# secondary_DIO.net
KiCad netlist of a schematic drawn in Altium Designer
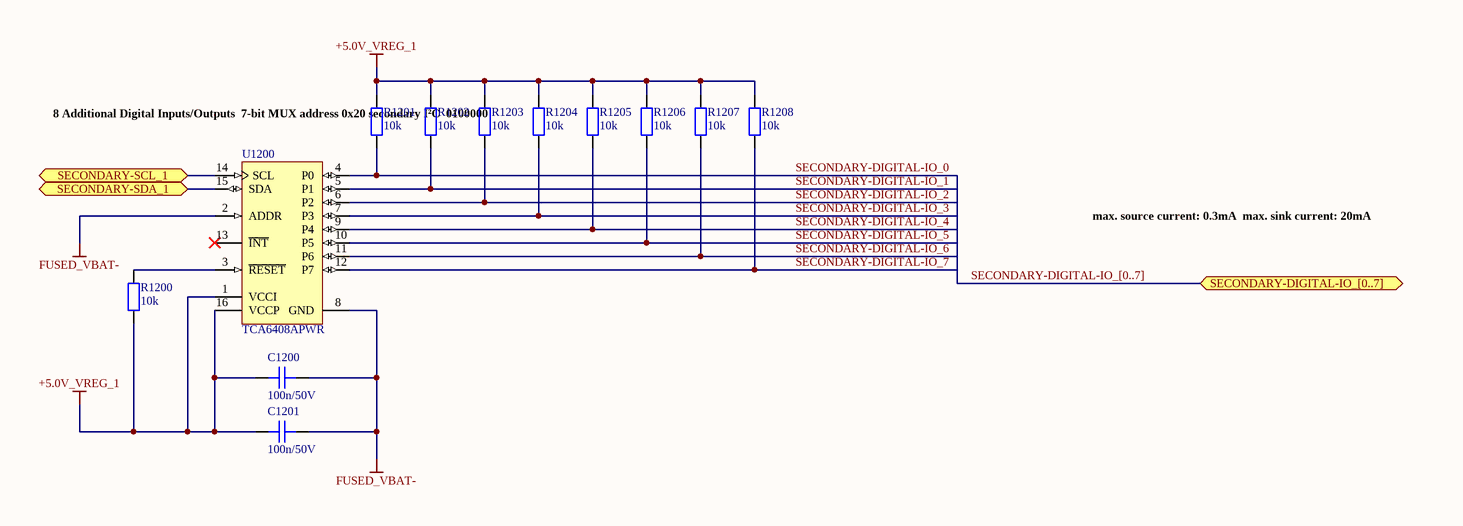
[diagram p0: secondary_DIO.SchDoc]

(export (version "E")
  (design (tool "Eeschema 10.0.6"))
  (components
    (comp (ref "C1200")
      (value "100n/50V")
      (footprint "CAPC1608X08N")
      (description "MLCC")
      (fields (field (name "PART NUMBER") "gen_C_ceramic_100n_50V_X7R_0603"))
      (libsource (lib "OE750") (part "C"))
    )
    (comp (ref "C1201")
      (value "100n/50V")
      (footprint "CAPC1608X08N")
      (description "MLCC")
      (fields (field (name "PART NUMBER") "gen_C_ceramic_100n_50V_X7R_0603"))
      (libsource (lib "OE750") (part "C"))
    )
    (comp (ref "R1200")
      (value "10k")
      (footprint "RESC1608X05N")
      (description "SMD Resistor 10k 0603")
      (fields (field (name "PART NUMBER") "gen_R_10k_0603") (field (name "TOLERANCE") "1%"))
      (libsource (lib "OE750") (part "R"))
    )
    (comp (ref "R1201")
      (value "10k")
      (footprint "RESC1608X05N")
      (description "SMD Resistor 10k 0603")
      (fields (field (name "PART NUMBER") "gen_R_10k_0603") (field (name "TOLERANCE") "1%"))
      (libsource (lib "OE750") (part "R"))
    )
    (comp (ref "R1202")
      (value "10k")
      (footprint "RESC1608X05N")
      (description "SMD Resistor 10k 0603")
      (fields (field (name "PART NUMBER") "gen_R_10k_0603") (field (name "TOLERANCE") "1%"))
      (libsource (lib "OE750") (part "R"))
    )
    (comp (ref "R1203")
      (value "10k")
      (footprint "RESC1608X05N")
      (description "SMD Resistor 10k 0603")
      (fields (field (name "PART NUMBER") "gen_R_10k_0603") (field (name "TOLERANCE") "1%"))
      (libsource (lib "OE750") (part "R"))
    )
    (comp (ref "R1204")
      (value "10k")
      (footprint "RESC1608X05N")
      (description "SMD Resistor 10k 0603")
      (fields (field (name "PART NUMBER") "gen_R_10k_0603") (field (name "TOLERANCE") "1%"))
      (libsource (lib "OE750") (part "R"))
    )
    (comp (ref "R1205")
      (value "10k")
      (footprint "RESC1608X05N")
      (description "SMD Resistor 10k 0603")
      (fields (field (name "PART NUMBER") "gen_R_10k_0603") (field (name "TOLERANCE") "1%"))
      (libsource (lib "OE750") (part "R"))
    )
    (comp (ref "R1206")
      (value "10k")
      (footprint "RESC1608X05N")
      (description "SMD Resistor 10k 0603")
      (fields (field (name "PART NUMBER") "gen_R_10k_0603") (field (name "TOLERANCE") "1%"))
      (libsource (lib "OE750") (part "R"))
    )
    (comp (ref "R1207")
      (value "10k")
      (footprint "RESC1608X05N")
      (description "SMD Resistor 10k 0603")
      (fields (field (name "PART NUMBER") "gen_R_10k_0603") (field (name "TOLERANCE") "1%"))
      (libsource (lib "OE750") (part "R"))
    )
    (comp (ref "R1208")
      (value "10k")
      (footprint "RESC1608X05N")
      (description "SMD Resistor 10k 0603")
      (fields (field (name "PART NUMBER") "gen_R_10k_0603") (field (name "TOLERANCE") "1%"))
      (libsource (lib "OE750") (part "R"))
    )
    (comp (ref "U1200")
      (value "TCA6408APWR")
      (footprint "PW0016A_L")
      (fields (field (name "MANUFACTURER") "Texas Instruments"))
      (libsource (lib "Altium Content Vault") (part "TI-TCA6408A-TSSOP_PW-16"))
    )
  )
  (nets
    (net (code "1") (name "+5.0V_VREG_1") (class "Default")
      (node (ref "C1200") (pin "2") (pinfunction "2_2") (pintype "passive"))
      (node (ref "C1201") (pin "2") (pinfunction "2_2") (pintype "passive"))
      (node (ref "R1200") (pin "1") (pinfunction "1_1") (pintype "passive"))
      (node (ref "R1201") (pin "2") (pinfunction "2_2") (pintype "passive"))
      (node (ref "R1202") (pin "2") (pinfunction "2_2") (pintype "passive"))
      (node (ref "R1203") (pin "2") (pinfunction "2_2") (pintype "passive"))
      (node (ref "R1204") (pin "2") (pinfunction "2_2") (pintype "passive"))
      (node (ref "R1205") (pin "2") (pinfunction "2_2") (pintype "passive"))
      (node (ref "R1206") (pin "2") (pinfunction "2_2") (pintype "passive"))
      (node (ref "R1207") (pin "2") (pinfunction "2_2") (pintype "passive"))
      (node (ref "R1208") (pin "2") (pinfunction "2_2") (pintype "passive"))
      (node (ref "U1200") (pin "1") (pinfunction "VCCI_1") (pintype "power_in"))
      (node (ref "U1200") (pin "16") (pinfunction "VCCP_16") (pintype "power_in"))
    )
    (net (code "2") (name "/SECONDARY-DIGITAL-IO_0") (class "Default")
      (node (ref "R1201") (pin "1") (pinfunction "1_1") (pintype "passive"))
      (node (ref "U1200") (pin "4") (pinfunction "P0_4") (pintype "bidirectional"))
    )
    (net (code "3") (name "/SECONDARY-DIGITAL-IO_1") (class "Default")
      (node (ref "R1202") (pin "1") (pinfunction "1_1") (pintype "passive"))
      (node (ref "U1200") (pin "5") (pinfunction "P1_5") (pintype "bidirectional"))
    )
    (net (code "4") (name "/SECONDARY-DIGITAL-IO_2") (class "Default")
      (node (ref "R1203") (pin "1") (pinfunction "1_1") (pintype "passive"))
      (node (ref "U1200") (pin "6") (pinfunction "P2_6") (pintype "bidirectional"))
    )
    (net (code "5") (name "/SECONDARY-DIGITAL-IO_3") (class "Default")
      (node (ref "R1204") (pin "1") (pinfunction "1_1") (pintype "passive"))
      (node (ref "U1200") (pin "7") (pinfunction "P3_7") (pintype "bidirectional"))
    )
    (net (code "6") (name "/SECONDARY-DIGITAL-IO_4") (class "Default")
      (node (ref "R1205") (pin "1") (pinfunction "1_1") (pintype "passive"))
      (node (ref "U1200") (pin "9") (pinfunction "P4_9") (pintype "bidirectional"))
    )
    (net (code "7") (name "/SECONDARY-DIGITAL-IO_5") (class "Default")
      (node (ref "R1206") (pin "1") (pinfunction "1_1") (pintype "passive"))
      (node (ref "U1200") (pin "10") (pinfunction "P5_10") (pintype "bidirectional"))
    )
    (net (code "8") (name "/SECONDARY-DIGITAL-IO_6") (class "Default")
      (node (ref "R1207") (pin "1") (pinfunction "1_1") (pintype "passive"))
      (node (ref "U1200") (pin "11") (pinfunction "P6_11") (pintype "bidirectional"))
    )
    (net (code "9") (name "/SECONDARY-DIGITAL-IO_7") (class "Default")
      (node (ref "R1208") (pin "1") (pinfunction "1_1") (pintype "passive"))
      (node (ref "U1200") (pin "12") (pinfunction "P7_12") (pintype "bidirectional"))
    )
    (net (code "11") (name "/SECONDARY-SCL_1") (class "Default")
      (node (ref "U1200") (pin "14") (pinfunction "SCL_14") (pintype "input"))
    )
    (net (code "12") (name "/SECONDARY-SDA_1") (class "Default")
      (node (ref "U1200") (pin "15") (pinfunction "SDA_15") (pintype "bidirectional"))
    )
    (net (code "13") (name "FUSED_VBAT-") (class "Default")
      (node (ref "C1200") (pin "1") (pinfunction "1_1") (pintype "passive"))
      (node (ref "C1201") (pin "1") (pinfunction "1_1") (pintype "passive"))
      (node (ref "U1200") (pin "2") (pinfunction "ADDR_2") (pintype "input"))
      (node (ref "U1200") (pin "8") (pinfunction "GND_8") (pintype "power_in"))
    )
    (net (code "14") (name "Net-(U1200-~{RESET})") (class "Default")
      (node (ref "R1200") (pin "2") (pinfunction "2_2") (pintype "passive"))
      (node (ref "U1200") (pin "3") (pinfunction "~{RESET}_3") (pintype "input"))
    )
    (net (code "15") (name "unconnected-(U1200-~{INT}-Pad13)") (class "Default")
      (node (ref "U1200") (pin "13") (pinfunction "~{INT}_13") (pintype "open_collector+no_connect"))
    )
  )
)
